# energy-management-driver.net
KiCad netlist of a schematic drawn in EAGLE
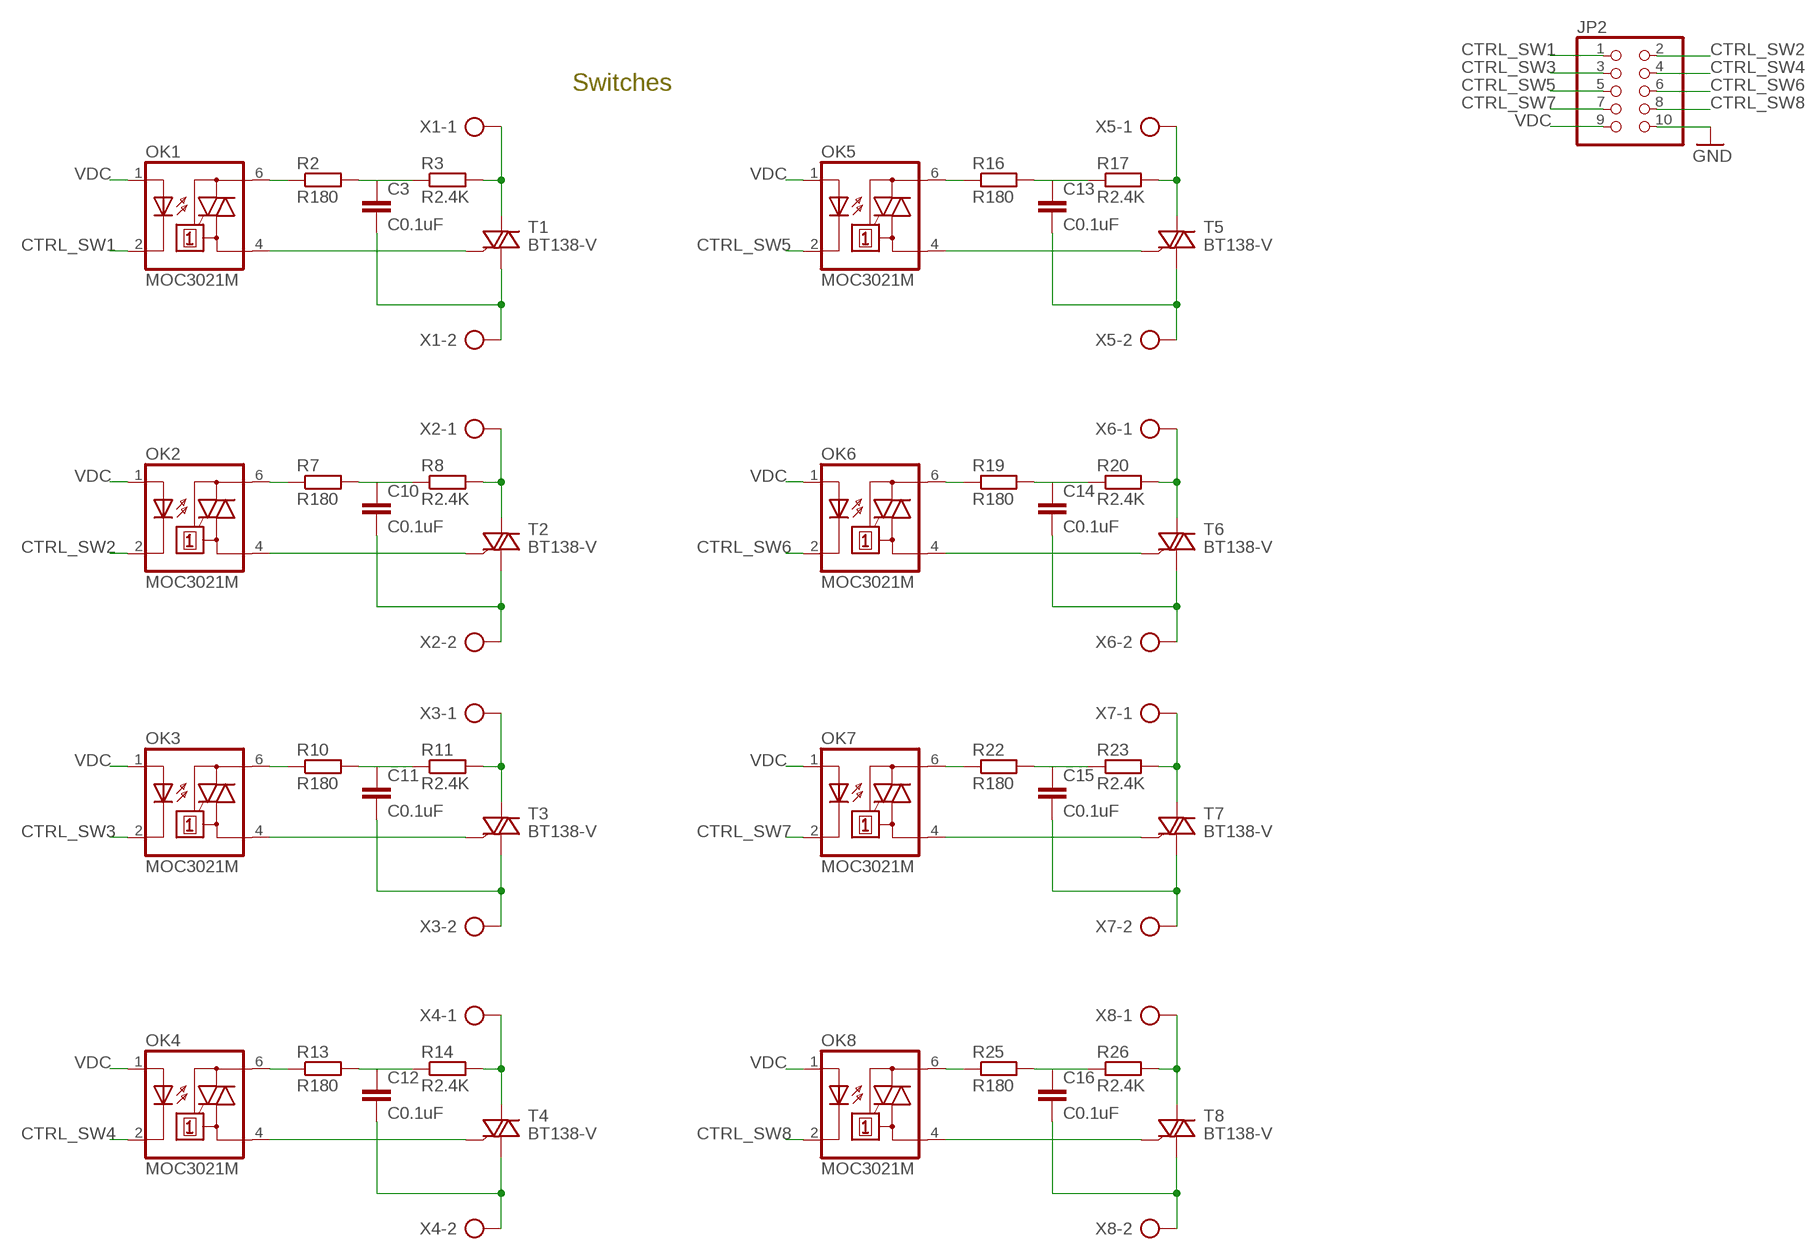
[diagram p0: schematic, sheet 1]

(export (version "E")
  (design (tool "Eeschema 10.0.6"))
  (components
    (comp (ref "C3")
      (value "C0.1uF")
      (footprint "eagle-import:C0805")
      (libsource (lib "eagle-import") (part "C-EUC0805"))
    )
    (comp (ref "C10")
      (value "C0.1uF")
      (footprint "eagle-import:C0805")
      (libsource (lib "eagle-import") (part "C-EUC0805"))
    )
    (comp (ref "C11")
      (value "C0.1uF")
      (footprint "eagle-import:C0805")
      (libsource (lib "eagle-import") (part "C-EUC0805"))
    )
    (comp (ref "C12")
      (value "C0.1uF")
      (footprint "eagle-import:C0805")
      (libsource (lib "eagle-import") (part "C-EUC0805"))
    )
    (comp (ref "C13")
      (value "C0.1uF")
      (footprint "eagle-import:C0805")
      (libsource (lib "eagle-import") (part "C-EUC0805"))
    )
    (comp (ref "C14")
      (value "C0.1uF")
      (footprint "eagle-import:C0805")
      (libsource (lib "eagle-import") (part "C-EUC0805"))
    )
    (comp (ref "C15")
      (value "C0.1uF")
      (footprint "eagle-import:C0805")
      (libsource (lib "eagle-import") (part "C-EUC0805"))
    )
    (comp (ref "C16")
      (value "C0.1uF")
      (footprint "eagle-import:C0805")
      (libsource (lib "eagle-import") (part "C-EUC0805"))
    )
    (comp (ref "JP2")
      (value "PINHD-2X5")
      (footprint "eagle-import:2X05")
      (libsource (lib "eagle-import") (part "PINHD-2X5"))
    )
    (comp (ref "OK1")
      (value "MOC3021M")
      (footprint "eagle-import:DIL06")
      (fields (field (name "MF") "FAIRCHILD SEMICONDUCTOR") (field (name "MPN") "MOC3021-M"))
      (libsource (lib "eagle-import") (part "MOC30M21"))
    )
    (comp (ref "OK2")
      (value "MOC3021M")
      (footprint "eagle-import:DIL06")
      (fields (field (name "MF") "FAIRCHILD SEMICONDUCTOR") (field (name "MPN") "MOC3021-M"))
      (libsource (lib "eagle-import") (part "MOC30M21"))
    )
    (comp (ref "OK3")
      (value "MOC3021M")
      (footprint "eagle-import:DIL06")
      (fields (field (name "MF") "FAIRCHILD SEMICONDUCTOR") (field (name "MPN") "MOC3021-M"))
      (libsource (lib "eagle-import") (part "MOC30M21"))
    )
    (comp (ref "OK4")
      (value "MOC3021M")
      (footprint "eagle-import:DIL06")
      (fields (field (name "MF") "FAIRCHILD SEMICONDUCTOR") (field (name "MPN") "MOC3021-M"))
      (libsource (lib "eagle-import") (part "MOC30M21"))
    )
    (comp (ref "OK5")
      (value "MOC3021M")
      (footprint "eagle-import:DIL06")
      (fields (field (name "MF") "FAIRCHILD SEMICONDUCTOR") (field (name "MPN") "MOC3021-M"))
      (libsource (lib "eagle-import") (part "MOC30M21"))
    )
    (comp (ref "OK6")
      (value "MOC3021M")
      (footprint "eagle-import:DIL06")
      (fields (field (name "MF") "FAIRCHILD SEMICONDUCTOR") (field (name "MPN") "MOC3021-M"))
      (libsource (lib "eagle-import") (part "MOC30M21"))
    )
    (comp (ref "OK7")
      (value "MOC3021M")
      (footprint "eagle-import:DIL06")
      (fields (field (name "MF") "FAIRCHILD SEMICONDUCTOR") (field (name "MPN") "MOC3021-M"))
      (libsource (lib "eagle-import") (part "MOC30M21"))
    )
    (comp (ref "OK8")
      (value "MOC3021M")
      (footprint "eagle-import:DIL06")
      (fields (field (name "MF") "FAIRCHILD SEMICONDUCTOR") (field (name "MPN") "MOC3021-M"))
      (libsource (lib "eagle-import") (part "MOC30M21"))
    )
    (comp (ref "R2")
      (value "R180")
      (footprint "eagle-import:M0805")
      (libsource (lib "eagle-import") (part "R-EU_M0805"))
    )
    (comp (ref "R3")
      (value "R2.4K")
      (footprint "eagle-import:M0805")
      (libsource (lib "eagle-import") (part "R-EU_M0805"))
    )
    (comp (ref "R7")
      (value "R180")
      (footprint "eagle-import:M0805")
      (libsource (lib "eagle-import") (part "R-EU_M0805"))
    )
    (comp (ref "R8")
      (value "R2.4K")
      (footprint "eagle-import:M0805")
      (libsource (lib "eagle-import") (part "R-EU_M0805"))
    )
    (comp (ref "R10")
      (value "R180")
      (footprint "eagle-import:M0805")
      (libsource (lib "eagle-import") (part "R-EU_M0805"))
    )
    (comp (ref "R11")
      (value "R2.4K")
      (footprint "eagle-import:M0805")
      (libsource (lib "eagle-import") (part "R-EU_M0805"))
    )
    (comp (ref "R13")
      (value "R180")
      (footprint "eagle-import:M0805")
      (libsource (lib "eagle-import") (part "R-EU_M0805"))
    )
    (comp (ref "R14")
      (value "R2.4K")
      (footprint "eagle-import:M0805")
      (libsource (lib "eagle-import") (part "R-EU_M0805"))
    )
    (comp (ref "R16")
      (value "R180")
      (footprint "eagle-import:M0805")
      (libsource (lib "eagle-import") (part "R-EU_M0805"))
    )
    (comp (ref "R17")
      (value "R2.4K")
      (footprint "eagle-import:M0805")
      (libsource (lib "eagle-import") (part "R-EU_M0805"))
    )
    (comp (ref "R19")
      (value "R180")
      (footprint "eagle-import:M0805")
      (libsource (lib "eagle-import") (part "R-EU_M0805"))
    )
    (comp (ref "R20")
      (value "R2.4K")
      (footprint "eagle-import:M0805")
      (libsource (lib "eagle-import") (part "R-EU_M0805"))
    )
    (comp (ref "R22")
      (value "R180")
      (footprint "eagle-import:M0805")
      (libsource (lib "eagle-import") (part "R-EU_M0805"))
    )
    (comp (ref "R23")
      (value "R2.4K")
      (footprint "eagle-import:M0805")
      (libsource (lib "eagle-import") (part "R-EU_M0805"))
    )
    (comp (ref "R25")
      (value "R180")
      (footprint "eagle-import:M0805")
      (libsource (lib "eagle-import") (part "R-EU_M0805"))
    )
    (comp (ref "R26")
      (value "R2.4K")
      (footprint "eagle-import:M0805")
      (libsource (lib "eagle-import") (part "R-EU_M0805"))
    )
    (comp (ref "T1")
      (value "BT138-V")
      (footprint "eagle-import:TO220BV")
      (libsource (lib "eagle-import") (part "BT138-V"))
    )
    (comp (ref "T2")
      (value "BT138-V")
      (footprint "eagle-import:TO220BV")
      (libsource (lib "eagle-import") (part "BT138-V"))
    )
    (comp (ref "T3")
      (value "BT138-V")
      (footprint "eagle-import:TO220BV")
      (libsource (lib "eagle-import") (part "BT138-V"))
    )
    (comp (ref "T4")
      (value "BT138-V")
      (footprint "eagle-import:TO220BV")
      (libsource (lib "eagle-import") (part "BT138-V"))
    )
    (comp (ref "T5")
      (value "BT138-V")
      (footprint "eagle-import:TO220BV")
      (libsource (lib "eagle-import") (part "BT138-V"))
    )
    (comp (ref "T6")
      (value "BT138-V")
      (footprint "eagle-import:TO220BV")
      (libsource (lib "eagle-import") (part "BT138-V"))
    )
    (comp (ref "T7")
      (value "BT138-V")
      (footprint "eagle-import:TO220BV")
      (libsource (lib "eagle-import") (part "BT138-V"))
    )
    (comp (ref "T8")
      (value "BT138-V")
      (footprint "eagle-import:TO220BV")
      (libsource (lib "eagle-import") (part "BT138-V"))
    )
    (comp (ref "X1")
      (value "AK300/2")
      (footprint "eagle-import:AK300_2")
      (libsource (lib "eagle-import") (part "AK300/2"))
    )
    (comp (ref "X2")
      (value "AK300/2")
      (footprint "eagle-import:AK300_2")
      (libsource (lib "eagle-import") (part "AK300/2"))
    )
    (comp (ref "X3")
      (value "AK300/2")
      (footprint "eagle-import:AK300_2")
      (libsource (lib "eagle-import") (part "AK300/2"))
    )
    (comp (ref "X4")
      (value "AK300/2")
      (footprint "eagle-import:AK300_2")
      (libsource (lib "eagle-import") (part "AK300/2"))
    )
    (comp (ref "X5")
      (value "AK300/2")
      (footprint "eagle-import:AK300_2")
      (libsource (lib "eagle-import") (part "AK300/2"))
    )
    (comp (ref "X6")
      (value "AK300/2")
      (footprint "eagle-import:AK300_2")
      (libsource (lib "eagle-import") (part "AK300/2"))
    )
    (comp (ref "X7")
      (value "AK300/2")
      (footprint "eagle-import:AK300_2")
      (libsource (lib "eagle-import") (part "AK300/2"))
    )
    (comp (ref "X8")
      (value "AK300/2")
      (footprint "eagle-import:AK300_2")
      (libsource (lib "eagle-import") (part "AK300/2"))
    )
  )
  (nets
    (net (code "1") (name "/CTRL_SW1") (class "Default")
      (node (ref "JP2") (pin "1") (pinfunction "1_1") (pintype "passive"))
      (node (ref "OK1") (pin "2") (pinfunction "C_2") (pintype "passive"))
    )
    (net (code "2") (name "/CTRL_SW2") (class "Default")
      (node (ref "JP2") (pin "2") (pinfunction "2_2") (pintype "passive"))
      (node (ref "OK2") (pin "2") (pinfunction "C_2") (pintype "passive"))
    )
    (net (code "3") (name "/CTRL_SW3") (class "Default")
      (node (ref "JP2") (pin "3") (pinfunction "3_3") (pintype "passive"))
      (node (ref "OK3") (pin "2") (pinfunction "C_2") (pintype "passive"))
    )
    (net (code "4") (name "/CTRL_SW4") (class "Default")
      (node (ref "JP2") (pin "4") (pinfunction "4_4") (pintype "passive"))
      (node (ref "OK4") (pin "2") (pinfunction "C_2") (pintype "passive"))
    )
    (net (code "5") (name "/CTRL_SW5") (class "Default")
      (node (ref "JP2") (pin "5") (pinfunction "5_5") (pintype "passive"))
      (node (ref "OK5") (pin "2") (pinfunction "C_2") (pintype "passive"))
    )
    (net (code "6") (name "/CTRL_SW6") (class "Default")
      (node (ref "JP2") (pin "6") (pinfunction "6_6") (pintype "passive"))
      (node (ref "OK6") (pin "2") (pinfunction "C_2") (pintype "passive"))
    )
    (net (code "7") (name "/CTRL_SW7") (class "Default")
      (node (ref "JP2") (pin "7") (pinfunction "7_7") (pintype "passive"))
      (node (ref "OK7") (pin "2") (pinfunction "C_2") (pintype "passive"))
    )
    (net (code "8") (name "/CTRL_SW8") (class "Default")
      (node (ref "JP2") (pin "8") (pinfunction "8_8") (pintype "passive"))
      (node (ref "OK8") (pin "2") (pinfunction "C_2") (pintype "passive"))
    )
    (net (code "9") (name "/VDC") (class "Default")
      (node (ref "JP2") (pin "9") (pinfunction "9_9") (pintype "passive"))
      (node (ref "OK1") (pin "1") (pinfunction "A_1") (pintype "passive"))
      (node (ref "OK2") (pin "1") (pinfunction "A_1") (pintype "passive"))
      (node (ref "OK3") (pin "1") (pinfunction "A_1") (pintype "passive"))
      (node (ref "OK4") (pin "1") (pinfunction "A_1") (pintype "passive"))
      (node (ref "OK5") (pin "1") (pinfunction "A_1") (pintype "passive"))
      (node (ref "OK6") (pin "1") (pinfunction "A_1") (pintype "passive"))
      (node (ref "OK7") (pin "1") (pinfunction "A_1") (pintype "passive"))
      (node (ref "OK8") (pin "1") (pinfunction "A_1") (pintype "passive"))
    )
    (net (code "10") (name "GND") (class "Default")
      (node (ref "JP2") (pin "10") (pinfunction "10_10") (pintype "passive"))
    )
    (net (code "11") (name "Net-(C3-Pad1)") (class "Default")
      (node (ref "C3") (pin "1") (pinfunction "1_1") (pintype "passive"))
      (node (ref "R2") (pin "2") (pinfunction "2_2") (pintype "passive"))
      (node (ref "R3") (pin "1") (pinfunction "1_1") (pintype "passive"))
    )
    (net (code "12") (name "Net-(C10-Pad1)") (class "Default")
      (node (ref "C10") (pin "1") (pinfunction "1_1") (pintype "passive"))
      (node (ref "R7") (pin "2") (pinfunction "2_2") (pintype "passive"))
      (node (ref "R8") (pin "1") (pinfunction "1_1") (pintype "passive"))
    )
    (net (code "13") (name "Net-(C11-Pad1)") (class "Default")
      (node (ref "C11") (pin "1") (pinfunction "1_1") (pintype "passive"))
      (node (ref "R10") (pin "2") (pinfunction "2_2") (pintype "passive"))
      (node (ref "R11") (pin "1") (pinfunction "1_1") (pintype "passive"))
    )
    (net (code "14") (name "Net-(C12-Pad1)") (class "Default")
      (node (ref "C12") (pin "1") (pinfunction "1_1") (pintype "passive"))
      (node (ref "R13") (pin "2") (pinfunction "2_2") (pintype "passive"))
      (node (ref "R14") (pin "1") (pinfunction "1_1") (pintype "passive"))
    )
    (net (code "15") (name "Net-(C13-Pad1)") (class "Default")
      (node (ref "C13") (pin "1") (pinfunction "1_1") (pintype "passive"))
      (node (ref "R16") (pin "2") (pinfunction "2_2") (pintype "passive"))
      (node (ref "R17") (pin "1") (pinfunction "1_1") (pintype "passive"))
    )
    (net (code "16") (name "Net-(C14-Pad1)") (class "Default")
      (node (ref "C14") (pin "1") (pinfunction "1_1") (pintype "passive"))
      (node (ref "R19") (pin "2") (pinfunction "2_2") (pintype "passive"))
      (node (ref "R20") (pin "1") (pinfunction "1_1") (pintype "passive"))
    )
    (net (code "17") (name "Net-(C15-Pad1)") (class "Default")
      (node (ref "C15") (pin "1") (pinfunction "1_1") (pintype "passive"))
      (node (ref "R22") (pin "2") (pinfunction "2_2") (pintype "passive"))
      (node (ref "R23") (pin "1") (pinfunction "1_1") (pintype "passive"))
    )
    (net (code "18") (name "Net-(C16-Pad1)") (class "Default")
      (node (ref "C16") (pin "1") (pinfunction "1_1") (pintype "passive"))
      (node (ref "R25") (pin "2") (pinfunction "2_2") (pintype "passive"))
      (node (ref "R26") (pin "1") (pinfunction "1_1") (pintype "passive"))
    )
    (net (code "19") (name "Net-(OK1-A1)") (class "Default")
      (node (ref "OK1") (pin "4") (pinfunction "A1_4") (pintype "passive"))
      (node (ref "T1") (pin "G") (pinfunction "G_G") (pintype "passive"))
    )
    (net (code "20") (name "Net-(OK1-A2)") (class "Default")
      (node (ref "OK1") (pin "6") (pinfunction "A2_6") (pintype "passive"))
      (node (ref "R2") (pin "1") (pinfunction "1_1") (pintype "passive"))
    )
    (net (code "21") (name "Net-(OK2-A1)") (class "Default")
      (node (ref "OK2") (pin "4") (pinfunction "A1_4") (pintype "passive"))
      (node (ref "T2") (pin "G") (pinfunction "G_G") (pintype "passive"))
    )
    (net (code "22") (name "Net-(OK2-A2)") (class "Default")
      (node (ref "OK2") (pin "6") (pinfunction "A2_6") (pintype "passive"))
      (node (ref "R7") (pin "1") (pinfunction "1_1") (pintype "passive"))
    )
    (net (code "23") (name "Net-(OK3-A1)") (class "Default")
      (node (ref "OK3") (pin "4") (pinfunction "A1_4") (pintype "passive"))
      (node (ref "T3") (pin "G") (pinfunction "G_G") (pintype "passive"))
    )
    (net (code "24") (name "Net-(OK3-A2)") (class "Default")
      (node (ref "OK3") (pin "6") (pinfunction "A2_6") (pintype "passive"))
      (node (ref "R10") (pin "1") (pinfunction "1_1") (pintype "passive"))
    )
    (net (code "25") (name "Net-(OK4-A1)") (class "Default")
      (node (ref "OK4") (pin "4") (pinfunction "A1_4") (pintype "passive"))
      (node (ref "T4") (pin "G") (pinfunction "G_G") (pintype "passive"))
    )
    (net (code "26") (name "Net-(OK4-A2)") (class "Default")
      (node (ref "OK4") (pin "6") (pinfunction "A2_6") (pintype "passive"))
      (node (ref "R13") (pin "1") (pinfunction "1_1") (pintype "passive"))
    )
    (net (code "27") (name "Net-(OK5-A1)") (class "Default")
      (node (ref "OK5") (pin "4") (pinfunction "A1_4") (pintype "passive"))
      (node (ref "T5") (pin "G") (pinfunction "G_G") (pintype "passive"))
    )
    (net (code "28") (name "Net-(OK5-A2)") (class "Default")
      (node (ref "OK5") (pin "6") (pinfunction "A2_6") (pintype "passive"))
      (node (ref "R16") (pin "1") (pinfunction "1_1") (pintype "passive"))
    )
    (net (code "29") (name "Net-(OK6-A1)") (class "Default")
      (node (ref "OK6") (pin "4") (pinfunction "A1_4") (pintype "passive"))
      (node (ref "T6") (pin "G") (pinfunction "G_G") (pintype "passive"))
    )
    (net (code "30") (name "Net-(OK6-A2)") (class "Default")
      (node (ref "OK6") (pin "6") (pinfunction "A2_6") (pintype "passive"))
      (node (ref "R19") (pin "1") (pinfunction "1_1") (pintype "passive"))
    )
    (net (code "31") (name "Net-(OK7-A1)") (class "Default")
      (node (ref "OK7") (pin "4") (pinfunction "A1_4") (pintype "passive"))
      (node (ref "T7") (pin "G") (pinfunction "G_G") (pintype "passive"))
    )
    (net (code "32") (name "Net-(OK7-A2)") (class "Default")
      (node (ref "OK7") (pin "6") (pinfunction "A2_6") (pintype "passive"))
      (node (ref "R22") (pin "1") (pinfunction "1_1") (pintype "passive"))
    )
    (net (code "33") (name "Net-(OK8-A1)") (class "Default")
      (node (ref "OK8") (pin "4") (pinfunction "A1_4") (pintype "passive"))
      (node (ref "T8") (pin "G") (pinfunction "G_G") (pintype "passive"))
    )
    (net (code "34") (name "Net-(OK8-A2)") (class "Default")
      (node (ref "OK8") (pin "6") (pinfunction "A2_6") (pintype "passive"))
      (node (ref "R25") (pin "1") (pinfunction "1_1") (pintype "passive"))
    )
    (net (code "35") (name "Net-(T1-A1)") (class "Default")
      (node (ref "C3") (pin "2") (pinfunction "2_2") (pintype "passive"))
      (node (ref "T1") (pin "T1") (pinfunction "A1_T1") (pintype "passive"))
      (node (ref "X1") (pin "2") (pinfunction "KL_2") (pintype "passive"))
    )
    (net (code "36") (name "Net-(T1-A2)") (class "Default")
      (node (ref "R3") (pin "2") (pinfunction "2_2") (pintype "passive"))
      (node (ref "T1") (pin "T2") (pinfunction "A2_T2") (pintype "passive"))
      (node (ref "X1") (pin "1") (pinfunction "KL_1") (pintype "passive"))
    )
    (net (code "37") (name "Net-(T2-A1)") (class "Default")
      (node (ref "C10") (pin "2") (pinfunction "2_2") (pintype "passive"))
      (node (ref "T2") (pin "T1") (pinfunction "A1_T1") (pintype "passive"))
      (node (ref "X2") (pin "2") (pinfunction "KL_2") (pintype "passive"))
    )
    (net (code "38") (name "Net-(T2-A2)") (class "Default")
      (node (ref "R8") (pin "2") (pinfunction "2_2") (pintype "passive"))
      (node (ref "T2") (pin "T2") (pinfunction "A2_T2") (pintype "passive"))
      (node (ref "X2") (pin "1") (pinfunction "KL_1") (pintype "passive"))
    )
    (net (code "39") (name "Net-(T3-A1)") (class "Default")
      (node (ref "C11") (pin "2") (pinfunction "2_2") (pintype "passive"))
      (node (ref "T3") (pin "T1") (pinfunction "A1_T1") (pintype "passive"))
      (node (ref "X3") (pin "2") (pinfunction "KL_2") (pintype "passive"))
    )
    (net (code "40") (name "Net-(T3-A2)") (class "Default")
      (node (ref "R11") (pin "2") (pinfunction "2_2") (pintype "passive"))
      (node (ref "T3") (pin "T2") (pinfunction "A2_T2") (pintype "passive"))
      (node (ref "X3") (pin "1") (pinfunction "KL_1") (pintype "passive"))
    )
    (net (code "41") (name "Net-(T4-A1)") (class "Default")
      (node (ref "C12") (pin "2") (pinfunction "2_2") (pintype "passive"))
      (node (ref "T4") (pin "T1") (pinfunction "A1_T1") (pintype "passive"))
      (node (ref "X4") (pin "2") (pinfunction "KL_2") (pintype "passive"))
    )
    (net (code "42") (name "Net-(T4-A2)") (class "Default")
      (node (ref "R14") (pin "2") (pinfunction "2_2") (pintype "passive"))
      (node (ref "T4") (pin "T2") (pinfunction "A2_T2") (pintype "passive"))
      (node (ref "X4") (pin "1") (pinfunction "KL_1") (pintype "passive"))
    )
    (net (code "43") (name "Net-(T5-A1)") (class "Default")
      (node (ref "C13") (pin "2") (pinfunction "2_2") (pintype "passive"))
      (node (ref "T5") (pin "T1") (pinfunction "A1_T1") (pintype "passive"))
      (node (ref "X5") (pin "2") (pinfunction "KL_2") (pintype "passive"))
    )
    (net (code "44") (name "Net-(T5-A2)") (class "Default")
      (node (ref "R17") (pin "2") (pinfunction "2_2") (pintype "passive"))
      (node (ref "T5") (pin "T2") (pinfunction "A2_T2") (pintype "passive"))
      (node (ref "X5") (pin "1") (pinfunction "KL_1") (pintype "passive"))
    )
    (net (code "45") (name "Net-(T6-A1)") (class "Default")
      (node (ref "C14") (pin "2") (pinfunction "2_2") (pintype "passive"))
      (node (ref "T6") (pin "T1") (pinfunction "A1_T1") (pintype "passive"))
      (node (ref "X6") (pin "2") (pinfunction "KL_2") (pintype "passive"))
    )
    (net (code "46") (name "Net-(T6-A2)") (class "Default")
      (node (ref "R20") (pin "2") (pinfunction "2_2") (pintype "passive"))
      (node (ref "T6") (pin "T2") (pinfunction "A2_T2") (pintype "passive"))
      (node (ref "X6") (pin "1") (pinfunction "KL_1") (pintype "passive"))
    )
    (net (code "47") (name "Net-(T7-A1)") (class "Default")
      (node (ref "C15") (pin "2") (pinfunction "2_2") (pintype "passive"))
      (node (ref "T7") (pin "T1") (pinfunction "A1_T1") (pintype "passive"))
      (node (ref "X7") (pin "2") (pinfunction "KL_2") (pintype "passive"))
    )
    (net (code "48") (name "Net-(T7-A2)") (class "Default")
      (node (ref "R23") (pin "2") (pinfunction "2_2") (pintype "passive"))
      (node (ref "T7") (pin "T2") (pinfunction "A2_T2") (pintype "passive"))
      (node (ref "X7") (pin "1") (pinfunction "KL_1") (pintype "passive"))
    )
    (net (code "49") (name "Net-(T8-A1)") (class "Default")
      (node (ref "C16") (pin "2") (pinfunction "2_2") (pintype "passive"))
      (node (ref "T8") (pin "T1") (pinfunction "A1_T1") (pintype "passive"))
      (node (ref "X8") (pin "2") (pinfunction "KL_2") (pintype "passive"))
    )
    (net (code "50") (name "Net-(T8-A2)") (class "Default")
      (node (ref "R26") (pin "2") (pinfunction "2_2") (pintype "passive"))
      (node (ref "T8") (pin "T2") (pinfunction "A2_T2") (pintype "passive"))
      (node (ref "X8") (pin "1") (pinfunction "KL_1") (pintype "passive"))
    )
  )
)
